# SCH_Onboard-card_2024-03-05.net
KiCad netlist of a schematic drawn in EasyEDA
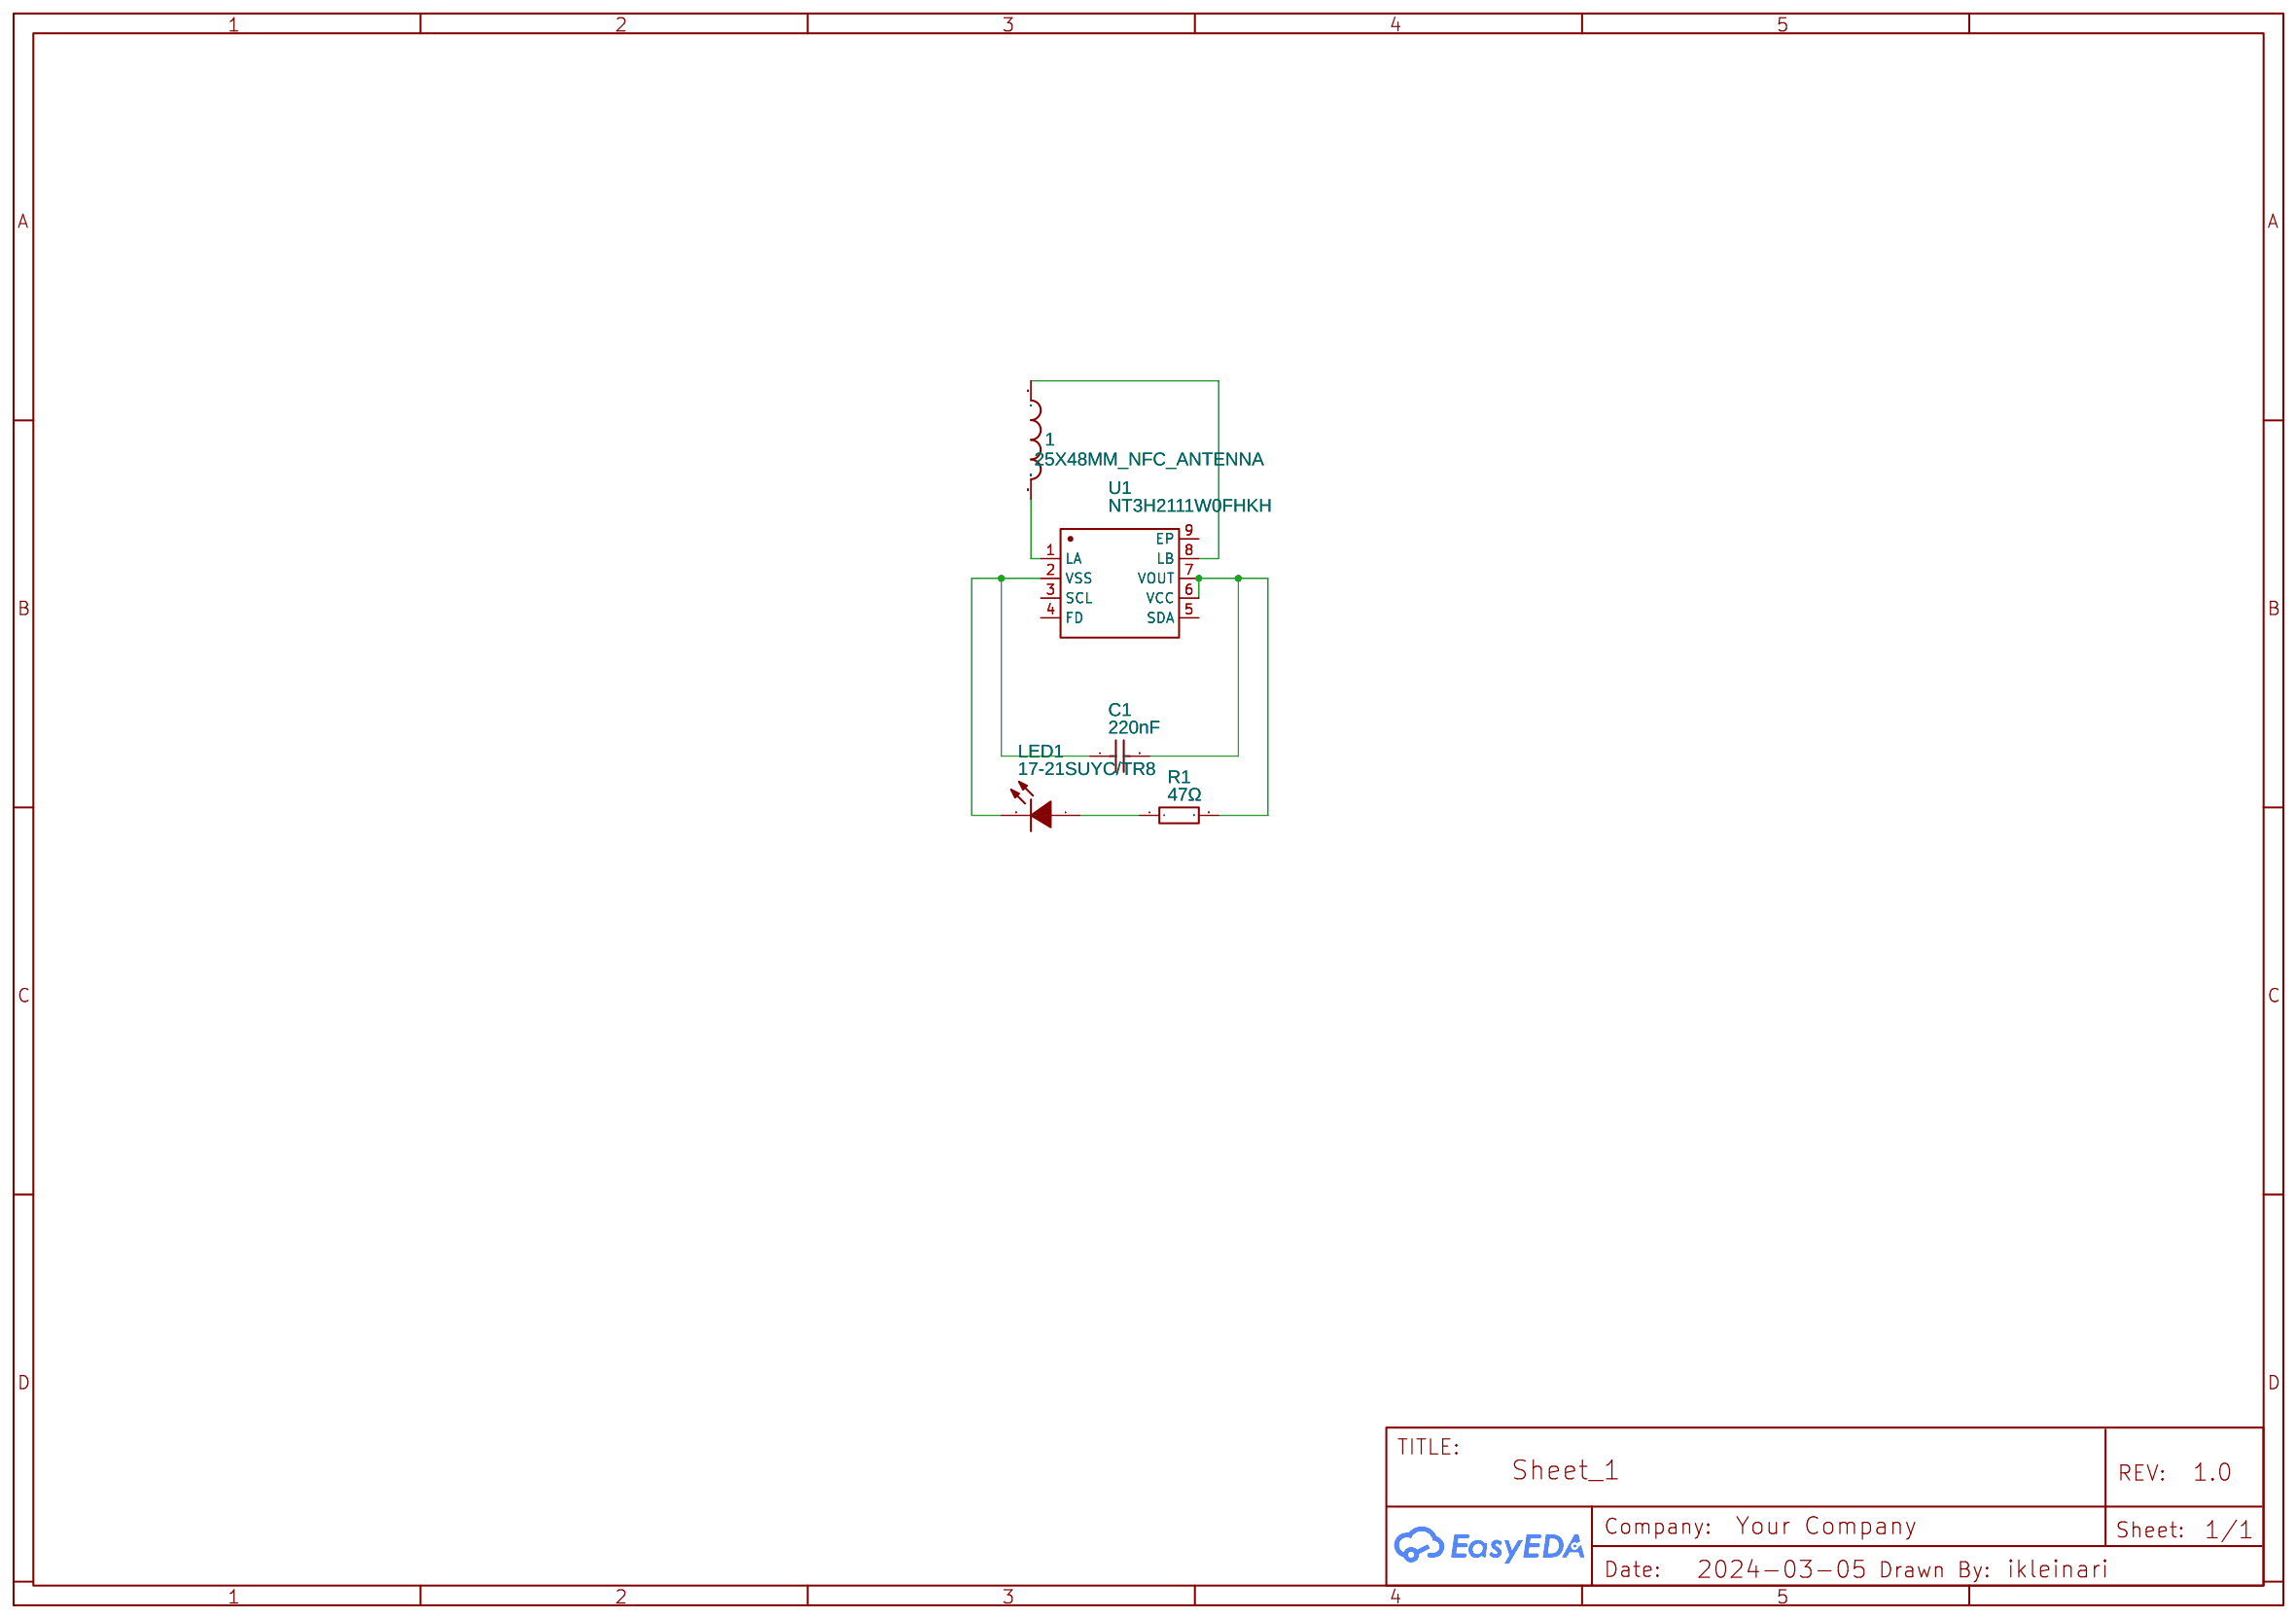
[diagram p0: schematic sheet]

(export (version "E")
  (design (tool "Eeschema 10.0.6"))
  (components
    (comp (ref "1") (value "25X48MM_NFC_ANTENNA") (libsource (lib "") (part "25X48MM_NFC_ANTENNA")))
    (comp (ref "C1")
      (value "220nF")
      (fields
        (field (name "Manufacturer Part") "CL10B224KA8NNNC")
        (field (name "Manufacturer") "SAMSUNG(三星)")
      )
      (libsource (lib "") (part "CL10B224KA8NNNC"))
    )
    (comp (ref "LED1")
      (value "17-21SUYC/TR8")
      (fields (field (name "Manufacturer Part") "KT-0805黄灯") (field (name "Manufacturer") "KENTO"))
      (libsource (lib "") (part "17-21SUYC/TR8"))
    )
    (comp (ref "R1")
      (value "47Ω")
      (fields
        (field (name "Manufacturer Part") "0603WAF470JT5E")
        (field (name "Manufacturer") "UNI-ROYAL(厚声)")
      )
      (libsource (lib "") (part "0603WAF470JT5E"))
    )
    (comp (ref "U1")
      (value "NT3H2111W0FHKH")
      (fields (field (name "Manufacturer") "NXP(恩智浦)"))
      (libsource (lib "") (part "NT3H2111W0FHKH"))
    )
  )
  (nets
    (net (code "1") (name "Net-(LED1-+)") (class "Default")
      (node (ref "LED1") (pin "1") (pinfunction "+_1") (pintype "unspecified"))
      (node (ref "R1") (pin "1") (pinfunction "1_1") (pintype "input"))
    )
    (net (code "2") (name "Net-(LED1--)") (class "Default")
      (node (ref "C1") (pin "1") (pinfunction "1_1") (pintype "input"))
      (node (ref "LED1") (pin "2") (pinfunction "-_2") (pintype "unspecified"))
      (node (ref "U1") (pin "2") (pinfunction "VSS_2") (pintype "unspecified"))
    )
    (net (code "3") (name "Net-(U1-LA)") (class "Default")
      (node (ref "1") (pin "P$2") (pinfunction "P$2_P$2") (pintype "bidirectional"))
      (node (ref "U1") (pin "1") (pinfunction "LA_1") (pintype "unspecified"))
    )
    (net (code "4") (name "Net-(U1-LB)") (class "Default")
      (node (ref "1") (pin "P$1") (pinfunction "P$1_P$1") (pintype "bidirectional"))
      (node (ref "U1") (pin "8") (pinfunction "LB_8") (pintype "unspecified"))
    )
    (net (code "5") (name "Net-(U1-VCC)") (class "Default")
      (node (ref "C1") (pin "2") (pinfunction "2_2") (pintype "input"))
      (node (ref "R1") (pin "2") (pinfunction "2_2") (pintype "input"))
      (node (ref "U1") (pin "6") (pinfunction "VCC_6") (pintype "unspecified"))
      (node (ref "U1") (pin "7") (pinfunction "VOUT_7") (pintype "unspecified"))
    )
    (net (code "6") (name "unconnected-(U1-EP-Pad9)") (class "Default")
      (node (ref "U1") (pin "9") (pinfunction "EP_9") (pintype "unspecified"))
    )
    (net (code "7") (name "unconnected-(U1-FD-Pad4)") (class "Default")
      (node (ref "U1") (pin "4") (pinfunction "FD_4") (pintype "unspecified"))
    )
    (net (code "8") (name "unconnected-(U1-SCL-Pad3)") (class "Default")
      (node (ref "U1") (pin "3") (pinfunction "SCL_3") (pintype "unspecified"))
    )
    (net (code "9") (name "unconnected-(U1-SDA-Pad5)") (class "Default")
      (node (ref "U1") (pin "5") (pinfunction "SDA_5") (pintype "unspecified"))
    )
  )
)
